# Sheet1.net
KiCad netlist of a schematic drawn in Altium Designer
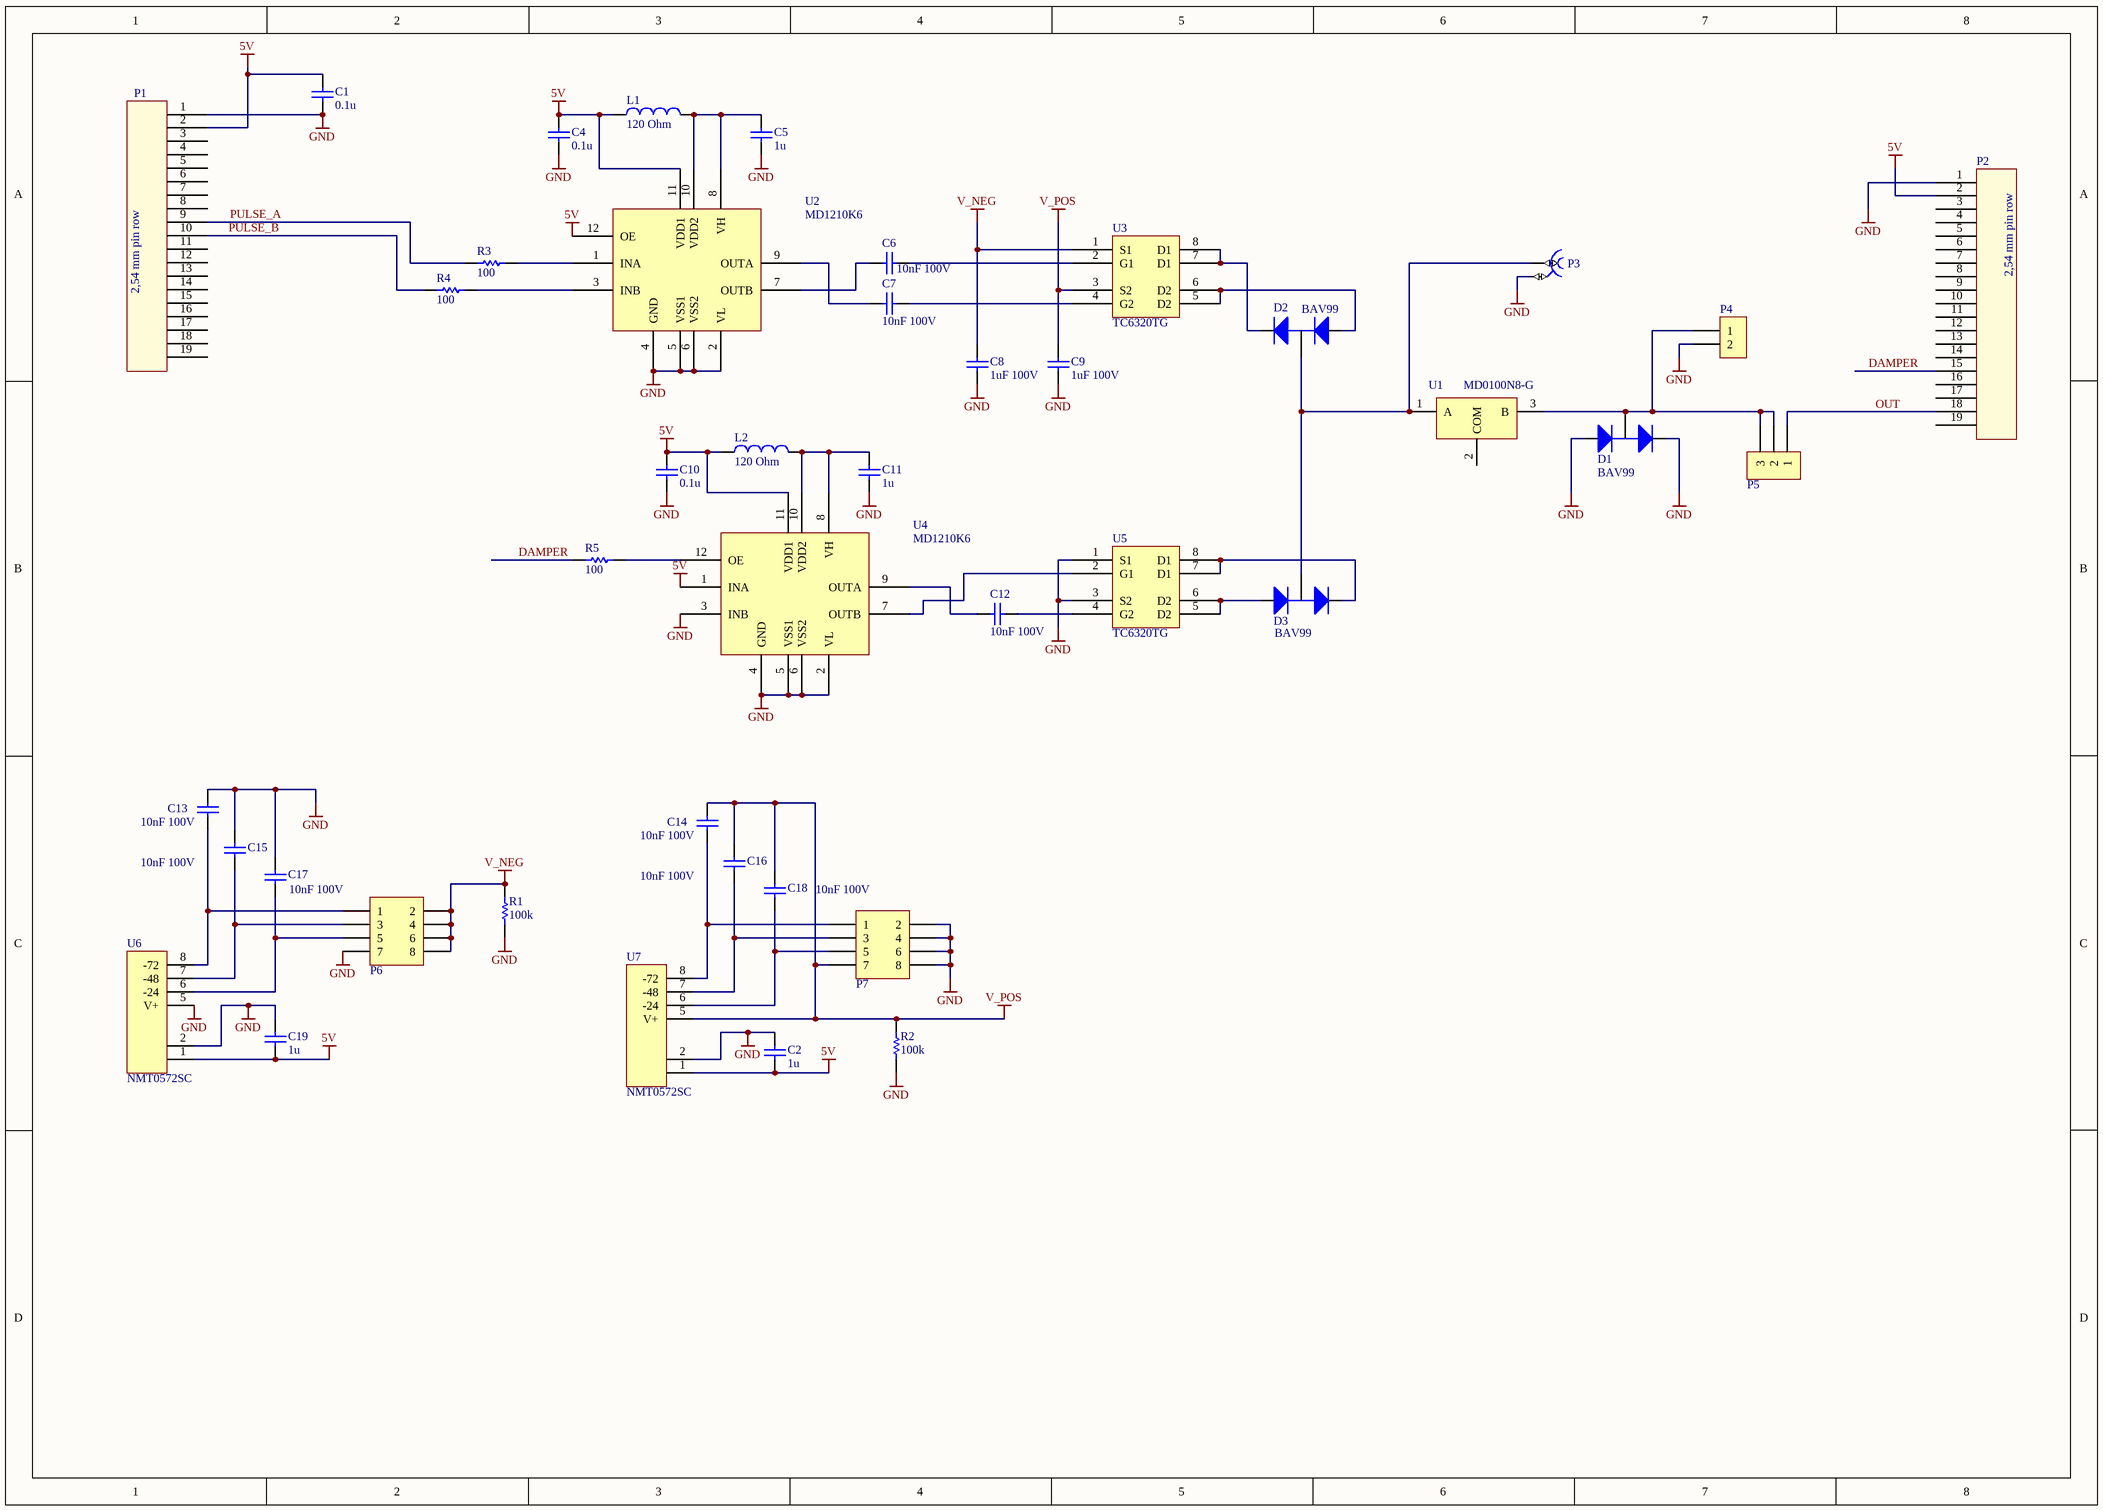
[diagram p0: Sheet1.SchDoc]

(export (version "E")
  (design (tool "Eeschema 10.0.6"))
  (components
    (comp (ref "C1")
      (value "0.1u")
      (footprint "0603RC")
      (description "Capacitor")
      (fields (field (name "PUBLISHER") "Altium Limited"))
      (libsource (lib "Miscellaneous Devices") (part "Cap"))
    )
    (comp (ref "C2")
      (value "1u")
      (footprint "0805RC")
      (description "Capacitor")
      (fields (field (name "PUBLISHER") "Altium Limited"))
      (libsource (lib "Miscellaneous Devices") (part "Cap"))
    )
    (comp (ref "C4")
      (value "0.1u")
      (footprint "0603RC")
      (description "Capacitor")
      (fields (field (name "PUBLISHER") "Altium Limited"))
      (libsource (lib "Miscellaneous Devices") (part "Cap"))
    )
    (comp (ref "C5")
      (value "1u")
      (footprint "0805RC")
      (description "Capacitor")
      (fields (field (name "PUBLISHER") "Altium Limited"))
      (libsource (lib "Miscellaneous Devices") (part "Cap"))
    )
    (comp (ref "C6")
      (value "10nF 100V")
      (footprint "0805RC")
      (description "Capacitor")
      (fields (field (name "PUBLISHER") "Altium Limited"))
      (libsource (lib "Miscellaneous Devices") (part "Cap"))
    )
    (comp (ref "C7")
      (value "10nF 100V")
      (footprint "0805RC")
      (description "Capacitor")
      (fields (field (name "PUBLISHER") "Altium Limited"))
      (libsource (lib "Miscellaneous Devices") (part "Cap"))
    )
    (comp (ref "C8")
      (value "1uF 100V")
      (footprint "1206RC")
      (description "Capacitor")
      (fields (field (name "PUBLISHER") "Altium Limited"))
      (libsource (lib "Miscellaneous Devices") (part "Cap"))
    )
    (comp (ref "C9")
      (value "1uF 100V")
      (footprint "1206RC")
      (description "Capacitor")
      (fields (field (name "PUBLISHER") "Altium Limited"))
      (libsource (lib "Miscellaneous Devices") (part "Cap"))
    )
    (comp (ref "C10")
      (value "0.1u")
      (footprint "0603RC")
      (description "Capacitor")
      (fields (field (name "PUBLISHER") "Altium Limited"))
      (libsource (lib "Miscellaneous Devices") (part "Cap"))
    )
    (comp (ref "C11")
      (value "1u")
      (footprint "0805RC")
      (description "Capacitor")
      (fields (field (name "PUBLISHER") "Altium Limited"))
      (libsource (lib "Miscellaneous Devices") (part "Cap"))
    )
    (comp (ref "C12")
      (value "10nF 100V")
      (footprint "0805RC")
      (description "Capacitor")
      (fields (field (name "PUBLISHER") "Altium Limited"))
      (libsource (lib "Miscellaneous Devices") (part "Cap"))
    )
    (comp (ref "C13")
      (value "10nF 100V")
      (footprint "0805RC")
      (description "Capacitor")
      (fields (field (name "PUBLISHER") "Altium Limited"))
      (libsource (lib "Miscellaneous Devices") (part "Cap"))
    )
    (comp (ref "C14")
      (value "10nF 100V")
      (footprint "0805RC")
      (description "Capacitor")
      (fields (field (name "PUBLISHER") "Altium Limited"))
      (libsource (lib "Miscellaneous Devices") (part "Cap"))
    )
    (comp (ref "C15")
      (value "10nF 100V")
      (footprint "0805RC")
      (description "Capacitor")
      (fields (field (name "PUBLISHER") "Altium Limited"))
      (libsource (lib "Miscellaneous Devices") (part "Cap"))
    )
    (comp (ref "C16")
      (value "10nF 100V")
      (footprint "0805RC")
      (description "Capacitor")
      (fields (field (name "PUBLISHER") "Altium Limited"))
      (libsource (lib "Miscellaneous Devices") (part "Cap"))
    )
    (comp (ref "C17")
      (value "10nF 100V")
      (footprint "0805RC")
      (description "Capacitor")
      (fields (field (name "PUBLISHER") "Altium Limited"))
      (libsource (lib "Miscellaneous Devices") (part "Cap"))
    )
    (comp (ref "C18")
      (value "10nF 100V")
      (footprint "0805RC")
      (description "Capacitor")
      (fields (field (name "PUBLISHER") "Altium Limited"))
      (libsource (lib "Miscellaneous Devices") (part "Cap"))
    )
    (comp (ref "C19")
      (value "1u")
      (footprint "0805RC")
      (description "Capacitor")
      (fields (field (name "PUBLISHER") "Altium Limited"))
      (libsource (lib "Miscellaneous Devices") (part "Cap"))
    )
    (comp (ref "D1")
      (value "BAV99")
      (footprint "SOT-23")
      (description "Medium-speed Switching Double Diode with Low Leakage Current")
      (fields (field (name "PUBLISHER") "Altium Limited"))
      (libsource (lib "Miscellaneous Devices") (part "BAV199"))
    )
    (comp (ref "D2")
      (value "BAV99")
      (footprint "SOT-23")
      (description "Medium-speed Switching Double Diode with Low Leakage Current")
      (fields (field (name "PUBLISHER") "Altium Limited"))
      (libsource (lib "Miscellaneous Devices") (part "BAV199"))
    )
    (comp (ref "D3")
      (value "BAV99")
      (footprint "SOT-23")
      (description "Medium-speed Switching Double Diode with Low Leakage Current")
      (fields (field (name "PUBLISHER") "Altium Limited"))
      (libsource (lib "Miscellaneous Devices") (part "BAV199"))
    )
    (comp (ref "L1")
      (value "120 Ohm")
      (footprint "0805R")
      (description "Inductor")
      (fields (field (name "Comment") "BLM21PG121SN1D") (field (name "PUBLISHER") "Altium Limited"))
      (libsource (lib "Miscellaneous Devices") (part "Inductor"))
    )
    (comp (ref "L2")
      (value "120 Ohm")
      (footprint "0805R")
      (description "Inductor")
      (fields (field (name "Comment") "BLM21PG121SN1D") (field (name "PUBLISHER") "Altium Limited"))
      (libsource (lib "Miscellaneous Devices") (part "Inductor"))
    )
    (comp (ref "P1")
      (value "PLS_2.54mm-19")
      (footprint "PLS_2.54mm-19")
      (libsource (lib "alt_vovan") (part "PLS_2.54mm-19"))
    )
    (comp (ref "P2")
      (value "PLS_2.54mm-19")
      (footprint "PLS_2.54mm-19")
      (libsource (lib "") (part "PLS_2.54mm-19_1"))
    )
    (comp (ref "P3")
      (value "SMA")
      (footprint "echOpen_ADC_Card:AMPHENOL_132357-11")
      (fields
        (field (name "PART NUMBER") "AMPHENOL_132357-11")
        (field (name "MANUFACTURER") "AMPHENOL")
        (field (name "MANUFACTURER PART NUMBER") "132357-11")
        (field (name "AUTHOR") "CERN DEM JLC")
      )
      (libsource (lib "Sof-Connectors") (part "Coax_1Female_1Shield"))
    )
    (comp (ref "P4")
      (value "SCSL-2")
      (footprint "SCSL-2")
      (description "2-pin general header")
      (fields (field (name "PUBLISHER") "Altium Limited"))
      (libsource (lib "Miscellaneous Devices") (part "Header 2"))
    )
    (comp (ref "P5")
      (value "PLS-3")
      (footprint "PLS-3")
      (description "3-pin general header")
      (fields (field (name "PUBLISHER") "Altium Limited"))
      (libsource (lib "Miscellaneous Devices") (part "Header 3"))
    )
    (comp (ref "P6")
      (value "PLD-8")
      (footprint "PLD-8")
      (description "Header, 4-Pin, Dual row")
      (fields (field (name "PUBLISHER") "Altium Limited"))
      (libsource (lib "Miscellaneous Devices") (part "Header 4X2"))
    )
    (comp (ref "P7")
      (value "PLD-8")
      (footprint "PLD-8")
      (description "Header, 4-Pin, Dual row")
      (fields (field (name "PUBLISHER") "Altium Limited"))
      (libsource (lib "Miscellaneous Devices") (part "Header 4X2"))
    )
    (comp (ref "R1")
      (value "100k")
      (footprint "0805R")
      (description "Resistor")
      (fields (field (name "PUBLISHER") "Altium Limited"))
      (libsource (lib "Miscellaneous Devices") (part "Res1"))
    )
    (comp (ref "R2")
      (value "100k")
      (footprint "0805R")
      (description "Resistor")
      (fields (field (name "PUBLISHER") "Altium Limited"))
      (libsource (lib "Miscellaneous Devices") (part "Res1"))
    )
    (comp (ref "R3")
      (value "100")
      (footprint "0603R")
      (description "Resistor")
      (fields (field (name "PUBLISHER") "Altium Limited"))
      (libsource (lib "Miscellaneous Devices") (part "Res1"))
    )
    (comp (ref "R4")
      (value "100")
      (footprint "0603R")
      (description "Resistor")
      (fields (field (name "PUBLISHER") "Altium Limited"))
      (libsource (lib "Miscellaneous Devices") (part "Res1"))
    )
    (comp (ref "R5")
      (value "100")
      (footprint "0603R")
      (description "Resistor")
      (fields (field (name "PUBLISHER") "Altium Limited"))
      (libsource (lib "Miscellaneous Devices") (part "Res1"))
    )
    (comp (ref "U1")
      (value "MD0100N8-G")
      (footprint "echOpen_ADC_Card:SOT89")
      (description "3-Ultra-Sound HV Switch 1=A 2=COM 3=B")
      (fields (field (name "MANUFACTURER") "Supertex inc.") (field (name "AUTHOR") "S. Jafar"))
      (libsource (lib "Sof-ICs And Semiconductors") (part "MD0100"))
    )
    (comp (ref "U2") (value "MD1210K6") (footprint "QFN-12 4x4mm") (libsource (lib "Pulser") (part "MD1210")))
    (comp (ref "U3")
      (value "TC6320TG")
      (footprint "SOIC127P600-8N")
      (description "N- and P-Channel  Enhancement-Mode MOSFET Pair")
      (libsource (lib "Pulser") (part "TC6320"))
    )
    (comp (ref "U4") (value "MD1210K6") (footprint "QFN-12 4x4mm") (libsource (lib "Pulser") (part "MD1210")))
    (comp (ref "U5")
      (value "TC6320TG")
      (footprint "SOIC127P600-8N")
      (description "N- and P-Channel  Enhancement-Mode MOSFET Pair")
      (libsource (lib "Pulser") (part "TC6320"))
    )
    (comp (ref "U6")
      (value "NMT0572SC")
      (footprint "NMT0572SC")
      (description "Horizontal")
      (fields (field (name "PUBLISHER") "Altium Limited"))
      (libsource (lib "Miscellaneous Devices") (part "Header 8"))
    )
    (comp (ref "U7")
      (value "NMT0572SC")
      (footprint "NMT0572SC")
      (description "Horizontal")
      (fields (field (name "PUBLISHER") "Altium Limited"))
      (libsource (lib "Miscellaneous Devices") (part "Header 8"))
    )
  )
  (nets
    (net (code "1") (name "/DAMPER") (class "Default")
      (node (ref "P2") (pin "15") (pinfunction "15_15") (pintype "passive"))
      (node (ref "R5") (pin "1") (pinfunction "1_1") (pintype "passive"))
    )
    (net (code "3") (name "/PULSE_A") (class "Default")
      (node (ref "P1") (pin "9") (pinfunction "9_9") (pintype "passive"))
      (node (ref "R3") (pin "1") (pinfunction "1_1") (pintype "passive"))
    )
    (net (code "4") (name "/PULSE_B") (class "Default")
      (node (ref "P1") (pin "10") (pinfunction "10_10") (pintype "passive"))
      (node (ref "R4") (pin "1") (pinfunction "1_1") (pintype "passive"))
    )
    (net (code "5") (name "5V") (class "Default")
      (node (ref "C1") (pin "2") (pinfunction "2_2") (pintype "passive"))
      (node (ref "C10") (pin "2") (pinfunction "2_2") (pintype "passive"))
      (node (ref "C19") (pin "1") (pinfunction "1_1") (pintype "passive"))
      (node (ref "C2") (pin "1") (pinfunction "1_1") (pintype "passive"))
      (node (ref "C4") (pin "2") (pinfunction "2_2") (pintype "passive"))
      (node (ref "L1") (pin "1") (pinfunction "1_1") (pintype "passive"))
      (node (ref "L2") (pin "1") (pinfunction "1_1") (pintype "passive"))
      (node (ref "P1") (pin "2") (pinfunction "2_2") (pintype "passive"))
      (node (ref "P2") (pin "2") (pinfunction "2_2") (pintype "passive"))
      (node (ref "U2") (pin "11") (pinfunction "VDD1_11") (pintype "passive"))
      (node (ref "U2") (pin "12") (pinfunction "OE_12") (pintype "passive"))
      (node (ref "U4") (pin "1") (pinfunction "INA_1") (pintype "passive"))
      (node (ref "U4") (pin "11") (pinfunction "VDD1_11") (pintype "passive"))
      (node (ref "U6") (pin "1") (pinfunction "1_1") (pintype "passive"))
      (node (ref "U7") (pin "1") (pinfunction "1_1") (pintype "passive"))
    )
    (net (code "6") (name "GND") (class "Default")
      (node (ref "C1") (pin "1") (pinfunction "1_1") (pintype "passive"))
      (node (ref "C10") (pin "1") (pinfunction "1_1") (pintype "passive"))
      (node (ref "C11") (pin "1") (pinfunction "1_1") (pintype "passive"))
      (node (ref "C13") (pin "1") (pinfunction "1_1") (pintype "passive"))
      (node (ref "C15") (pin "1") (pinfunction "1_1") (pintype "passive"))
      (node (ref "C17") (pin "1") (pinfunction "1_1") (pintype "passive"))
      (node (ref "C19") (pin "2") (pinfunction "2_2") (pintype "passive"))
      (node (ref "C2") (pin "2") (pinfunction "2_2") (pintype "passive"))
      (node (ref "C4") (pin "1") (pinfunction "1_1") (pintype "passive"))
      (node (ref "C5") (pin "1") (pinfunction "1_1") (pintype "passive"))
      (node (ref "C8") (pin "1") (pinfunction "1_1") (pintype "passive"))
      (node (ref "C9") (pin "1") (pinfunction "1_1") (pintype "passive"))
      (node (ref "D1") (pin "1") (pinfunction "A_1") (pintype "passive"))
      (node (ref "D1") (pin "2") (pinfunction "K_2") (pintype "passive"))
      (node (ref "P1") (pin "1") (pinfunction "1_1") (pintype "passive"))
      (node (ref "P2") (pin "1") (pinfunction "1_1") (pintype "passive"))
      (node (ref "P3") (pin "2") (pinfunction "2_2") (pintype "bidirectional"))
      (node (ref "P4") (pin "2") (pinfunction "2_2") (pintype "passive"))
      (node (ref "P6") (pin "7") (pinfunction "7_7") (pintype "passive"))
      (node (ref "P7") (pin "2") (pinfunction "2_2") (pintype "passive"))
      (node (ref "P7") (pin "4") (pinfunction "4_4") (pintype "passive"))
      (node (ref "P7") (pin "6") (pinfunction "6_6") (pintype "passive"))
      (node (ref "P7") (pin "8") (pinfunction "8_8") (pintype "passive"))
      (node (ref "R1") (pin "1") (pinfunction "1_1") (pintype "passive"))
      (node (ref "R2") (pin "1") (pinfunction "1_1") (pintype "passive"))
      (node (ref "U2") (pin "2") (pinfunction "VL_2") (pintype "passive"))
      (node (ref "U2") (pin "4") (pinfunction "GND_4") (pintype "passive"))
      (node (ref "U2") (pin "5") (pinfunction "VSS1_5") (pintype "passive"))
      (node (ref "U2") (pin "6") (pinfunction "VSS2_6") (pintype "passive"))
      (node (ref "U4") (pin "2") (pinfunction "VL_2") (pintype "passive"))
      (node (ref "U4") (pin "3") (pinfunction "INB_3") (pintype "passive"))
      (node (ref "U4") (pin "4") (pinfunction "GND_4") (pintype "passive"))
      (node (ref "U4") (pin "5") (pinfunction "VSS1_5") (pintype "passive"))
      (node (ref "U4") (pin "6") (pinfunction "VSS2_6") (pintype "passive"))
      (node (ref "U5") (pin "1") (pinfunction "S1_1") (pintype "passive"))
      (node (ref "U5") (pin "3") (pinfunction "S2_3") (pintype "passive"))
      (node (ref "U6") (pin "2") (pinfunction "2_2") (pintype "passive"))
      (node (ref "U6") (pin "5") (pinfunction "V+_5") (pintype "passive"))
      (node (ref "U7") (pin "2") (pinfunction "2_2") (pintype "passive"))
    )
    (net (code "7") (name "Net-(D1-C)") (class "Default")
      (node (ref "D1") (pin "3") (pinfunction "C_3") (pintype "passive"))
      (node (ref "P4") (pin "1") (pinfunction "1_1") (pintype "passive"))
      (node (ref "P5") (pin "2") (pinfunction "2_2") (pintype "passive"))
      (node (ref "P5") (pin "3") (pinfunction "3_3") (pintype "passive"))
      (node (ref "U1") (pin "3") (pinfunction "B_3") (pintype "passive"))
    )
    (net (code "8") (name "Net-(D2-A)") (class "Default")
      (node (ref "D2") (pin "1") (pinfunction "A_1") (pintype "passive"))
      (node (ref "U3") (pin "5") (pinfunction "D2_5") (pintype "passive"))
      (node (ref "U3") (pin "6") (pinfunction "D2_6") (pintype "passive"))
    )
    (net (code "9") (name "Net-(D2-C)") (class "Default")
      (node (ref "D2") (pin "3") (pinfunction "C_3") (pintype "passive"))
      (node (ref "D3") (pin "3") (pinfunction "C_3") (pintype "passive"))
      (node (ref "P3") (pin "1") (pinfunction "1_1") (pintype "bidirectional"))
      (node (ref "U1") (pin "1") (pinfunction "A_1") (pintype "passive"))
    )
    (net (code "10") (name "Net-(D2-K)") (class "Default")
      (node (ref "D2") (pin "2") (pinfunction "K_2") (pintype "passive"))
      (node (ref "U3") (pin "7") (pinfunction "D1_7") (pintype "passive"))
      (node (ref "U3") (pin "8") (pinfunction "D1_8") (pintype "passive"))
    )
    (net (code "11") (name "Net-(D3-A)") (class "Default")
      (node (ref "D3") (pin "1") (pinfunction "A_1") (pintype "passive"))
      (node (ref "U5") (pin "5") (pinfunction "D2_5") (pintype "passive"))
      (node (ref "U5") (pin "6") (pinfunction "D2_6") (pintype "passive"))
    )
    (net (code "12") (name "Net-(D3-K)") (class "Default")
      (node (ref "D3") (pin "2") (pinfunction "K_2") (pintype "passive"))
      (node (ref "U5") (pin "7") (pinfunction "D1_7") (pintype "passive"))
      (node (ref "U5") (pin "8") (pinfunction "D1_8") (pintype "passive"))
    )
    (net (code "13") (name "Net-(P2-Pad18)") (class "Default")
      (node (ref "P2") (pin "18") (pinfunction "18_18") (pintype "passive"))
      (node (ref "P5") (pin "1") (pinfunction "1_1") (pintype "passive"))
    )
    (net (code "14") (name "Net-(U2-INA)") (class "Default")
      (node (ref "R3") (pin "2") (pinfunction "2_2") (pintype "passive"))
      (node (ref "U2") (pin "1") (pinfunction "INA_1") (pintype "passive"))
    )
    (net (code "15") (name "Net-(U2-INB)") (class "Default")
      (node (ref "R4") (pin "2") (pinfunction "2_2") (pintype "passive"))
      (node (ref "U2") (pin "3") (pinfunction "INB_3") (pintype "passive"))
    )
    (net (code "16") (name "Net-(U2-OUTA)") (class "Default")
      (node (ref "C7") (pin "2") (pinfunction "2_2") (pintype "passive"))
      (node (ref "U2") (pin "9") (pinfunction "OUTA_9") (pintype "passive"))
    )
    (net (code "17") (name "Net-(U2-OUTB)") (class "Default")
      (node (ref "C6") (pin "2") (pinfunction "2_2") (pintype "passive"))
      (node (ref "U2") (pin "7") (pinfunction "OUTB_7") (pintype "passive"))
    )
    (net (code "18") (name "Net-(U2-VDD2)") (class "Default")
      (node (ref "C5") (pin "2") (pinfunction "2_2") (pintype "passive"))
      (node (ref "L1") (pin "2") (pinfunction "2_2") (pintype "passive"))
      (node (ref "U2") (pin "10") (pinfunction "VDD2_10") (pintype "passive"))
      (node (ref "U2") (pin "8") (pinfunction "VH_8") (pintype "passive"))
    )
    (net (code "19") (name "Net-(U3-G1)") (class "Default")
      (node (ref "C6") (pin "1") (pinfunction "1_1") (pintype "passive"))
      (node (ref "U3") (pin "2") (pinfunction "G1_2") (pintype "passive"))
    )
    (net (code "20") (name "Net-(U3-G2)") (class "Default")
      (node (ref "C7") (pin "1") (pinfunction "1_1") (pintype "passive"))
      (node (ref "U3") (pin "4") (pinfunction "G2_4") (pintype "passive"))
    )
    (net (code "21") (name "Net-(U4-OE)") (class "Default")
      (node (ref "R5") (pin "2") (pinfunction "2_2") (pintype "passive"))
      (node (ref "U4") (pin "12") (pinfunction "OE_12") (pintype "passive"))
    )
    (net (code "22") (name "Net-(U4-OUTA)") (class "Default")
      (node (ref "C12") (pin "2") (pinfunction "2_2") (pintype "passive"))
      (node (ref "U4") (pin "9") (pinfunction "OUTA_9") (pintype "passive"))
    )
    (net (code "23") (name "Net-(U4-OUTB)") (class "Default")
      (node (ref "U4") (pin "7") (pinfunction "OUTB_7") (pintype "passive"))
      (node (ref "U5") (pin "2") (pinfunction "G1_2") (pintype "passive"))
    )
    (net (code "24") (name "Net-(U4-VDD2)") (class "Default")
      (node (ref "C11") (pin "2") (pinfunction "2_2") (pintype "passive"))
      (node (ref "L2") (pin "2") (pinfunction "2_2") (pintype "passive"))
      (node (ref "U4") (pin "10") (pinfunction "VDD2_10") (pintype "passive"))
      (node (ref "U4") (pin "8") (pinfunction "VH_8") (pintype "passive"))
    )
    (net (code "25") (name "Net-(U5-G2)") (class "Default")
      (node (ref "C12") (pin "1") (pinfunction "1_1") (pintype "passive"))
      (node (ref "U5") (pin "4") (pinfunction "G2_4") (pintype "passive"))
    )
    (net (code "26") (name "Net-(U6--24)") (class "Default")
      (node (ref "C17") (pin "2") (pinfunction "2_2") (pintype "passive"))
      (node (ref "P6") (pin "5") (pinfunction "5_5") (pintype "passive"))
      (node (ref "U6") (pin "6") (pinfunction "-24_6") (pintype "passive"))
    )
    (net (code "27") (name "Net-(U6--48)") (class "Default")
      (node (ref "C15") (pin "2") (pinfunction "2_2") (pintype "passive"))
      (node (ref "P6") (pin "3") (pinfunction "3_3") (pintype "passive"))
      (node (ref "U6") (pin "7") (pinfunction "-48_7") (pintype "passive"))
    )
    (net (code "28") (name "Net-(U6--72)") (class "Default")
      (node (ref "C13") (pin "2") (pinfunction "2_2") (pintype "passive"))
      (node (ref "P6") (pin "1") (pinfunction "1_1") (pintype "passive"))
      (node (ref "U6") (pin "8") (pinfunction "-72_8") (pintype "passive"))
    )
    (net (code "29") (name "Net-(U7--24)") (class "Default")
      (node (ref "C18") (pin "2") (pinfunction "2_2") (pintype "passive"))
      (node (ref "P7") (pin "5") (pinfunction "5_5") (pintype "passive"))
      (node (ref "U7") (pin "6") (pinfunction "-24_6") (pintype "passive"))
    )
    (net (code "30") (name "Net-(U7--48)") (class "Default")
      (node (ref "C16") (pin "2") (pinfunction "2_2") (pintype "passive"))
      (node (ref "P7") (pin "3") (pinfunction "3_3") (pintype "passive"))
      (node (ref "U7") (pin "7") (pinfunction "-48_7") (pintype "passive"))
    )
    (net (code "31") (name "Net-(U7--72)") (class "Default")
      (node (ref "C14") (pin "2") (pinfunction "2_2") (pintype "passive"))
      (node (ref "P7") (pin "1") (pinfunction "1_1") (pintype "passive"))
      (node (ref "U7") (pin "8") (pinfunction "-72_8") (pintype "passive"))
    )
    (net (code "32") (name "V_NEG") (class "Default")
      (node (ref "C8") (pin "2") (pinfunction "2_2") (pintype "passive"))
      (node (ref "P6") (pin "2") (pinfunction "2_2") (pintype "passive"))
      (node (ref "P6") (pin "4") (pinfunction "4_4") (pintype "passive"))
      (node (ref "P6") (pin "6") (pinfunction "6_6") (pintype "passive"))
      (node (ref "P6") (pin "8") (pinfunction "8_8") (pintype "passive"))
      (node (ref "R1") (pin "2") (pinfunction "2_2") (pintype "passive"))
      (node (ref "U3") (pin "1") (pinfunction "S1_1") (pintype "passive"))
    )
    (net (code "33") (name "V_POS") (class "Default")
      (node (ref "C14") (pin "1") (pinfunction "1_1") (pintype "passive"))
      (node (ref "C16") (pin "1") (pinfunction "1_1") (pintype "passive"))
      (node (ref "C18") (pin "1") (pinfunction "1_1") (pintype "passive"))
      (node (ref "C9") (pin "2") (pinfunction "2_2") (pintype "passive"))
      (node (ref "P7") (pin "7") (pinfunction "7_7") (pintype "passive"))
      (node (ref "R2") (pin "2") (pinfunction "2_2") (pintype "passive"))
      (node (ref "U3") (pin "3") (pinfunction "S2_3") (pintype "passive"))
      (node (ref "U7") (pin "5") (pinfunction "V+_5") (pintype "passive"))
    )
    (net (code "34") (name "unconnected-(P1-Pad3)") (class "Default")
      (node (ref "P1") (pin "3") (pinfunction "3_3") (pintype "passive"))
    )
    (net (code "35") (name "unconnected-(P1-Pad4)") (class "Default")
      (node (ref "P1") (pin "4") (pinfunction "4_4") (pintype "passive"))
    )
    (net (code "36") (name "unconnected-(P1-Pad5)") (class "Default")
      (node (ref "P1") (pin "5") (pinfunction "5_5") (pintype "passive"))
    )
    (net (code "37") (name "unconnected-(P1-Pad6)") (class "Default")
      (node (ref "P1") (pin "6") (pinfunction "6_6") (pintype "passive"))
    )
    (net (code "38") (name "unconnected-(P1-Pad7)") (class "Default")
      (node (ref "P1") (pin "7") (pinfunction "7_7") (pintype "passive"))
    )
    (net (code "39") (name "unconnected-(P1-Pad8)") (class "Default")
      (node (ref "P1") (pin "8") (pinfunction "8_8") (pintype "passive"))
    )
    (net (code "40") (name "unconnected-(P1-Pad11)") (class "Default")
      (node (ref "P1") (pin "11") (pinfunction "11_11") (pintype "passive"))
    )
    (net (code "41") (name "unconnected-(P1-Pad12)") (class "Default")
      (node (ref "P1") (pin "12") (pinfunction "12_12") (pintype "passive"))
    )
    (net (code "42") (name "unconnected-(P1-Pad13)") (class "Default")
      (node (ref "P1") (pin "13") (pinfunction "13_13") (pintype "passive"))
    )
    (net (code "43") (name "unconnected-(P1-Pad14)") (class "Default")
      (node (ref "P1") (pin "14") (pinfunction "14_14") (pintype "passive"))
    )
    (net (code "44") (name "unconnected-(P1-Pad15)") (class "Default")
      (node (ref "P1") (pin "15") (pinfunction "15_15") (pintype "passive"))
    )
    (net (code "45") (name "unconnected-(P1-Pad16)") (class "Default")
      (node (ref "P1") (pin "16") (pinfunction "16_16") (pintype "passive"))
    )
    (net (code "46") (name "unconnected-(P1-Pad17)") (class "Default")
      (node (ref "P1") (pin "17") (pinfunction "17_17") (pintype "passive"))
    )
    (net (code "47") (name "unconnected-(P1-Pad18)") (class "Default")
      (node (ref "P1") (pin "18") (pinfunction "18_18") (pintype "passive"))
    )
    (net (code "48") (name "unconnected-(P1-Pad19)") (class "Default")
      (node (ref "P1") (pin "19") (pinfunction "19_19") (pintype "passive"))
    )
    (net (code "49") (name "unconnected-(P2-Pad3)") (class "Default")
      (node (ref "P2") (pin "3") (pinfunction "3_3") (pintype "passive"))
    )
    (net (code "50") (name "unconnected-(P2-Pad4)") (class "Default")
      (node (ref "P2") (pin "4") (pinfunction "4_4") (pintype "passive"))
    )
    (net (code "51") (name "unconnected-(P2-Pad5)") (class "Default")
      (node (ref "P2") (pin "5") (pinfunction "5_5") (pintype "passive"))
    )
    (net (code "52") (name "unconnected-(P2-Pad6)") (class "Default")
      (node (ref "P2") (pin "6") (pinfunction "6_6") (pintype "passive"))
    )
    (net (code "53") (name "unconnected-(P2-Pad7)") (class "Default")
      (node (ref "P2") (pin "7") (pinfunction "7_7") (pintype "passive"))
    )
    (net (code "54") (name "unconnected-(P2-Pad8)") (class "Default")
      (node (ref "P2") (pin "8") (pinfunction "8_8") (pintype "passive"))
    )
    (net (code "55") (name "unconnected-(P2-Pad9)") (class "Default")
      (node (ref "P2") (pin "9") (pinfunction "9_9") (pintype "passive"))
    )
    (net (code "56") (name "unconnected-(P2-Pad10)") (class "Default")
      (node (ref "P2") (pin "10") (pinfunction "10_10") (pintype "passive"))
    )
    (net (code "57") (name "unconnected-(P2-Pad11)") (class "Default")
      (node (ref "P2") (pin "11") (pinfunction "11_11") (pintype "passive"))
    )
    (net (code "58") (name "unconnected-(P2-Pad12)") (class "Default")
      (node (ref "P2") (pin "12") (pinfunction "12_12") (pintype "passive"))
    )
    (net (code "59") (name "unconnected-(P2-Pad13)") (class "Default")
      (node (ref "P2") (pin "13") (pinfunction "13_13") (pintype "passive"))
    )
    (net (code "60") (name "unconnected-(P2-Pad14)") (class "Default")
      (node (ref "P2") (pin "14") (pinfunction "14_14") (pintype "passive"))
    )
    (net (code "61") (name "unconnected-(P2-Pad16)") (class "Default")
      (node (ref "P2") (pin "16") (pinfunction "16_16") (pintype "passive"))
    )
    (net (code "62") (name "unconnected-(P2-Pad17)") (class "Default")
      (node (ref "P2") (pin "17") (pinfunction "17_17") (pintype "passive"))
    )
    (net (code "63") (name "unconnected-(P2-Pad19)") (class "Default")
      (node (ref "P2") (pin "19") (pinfunction "19_19") (pintype "passive"))
    )
    (net (code "64") (name "unconnected-(U1-COM-Pad2)") (class "Default")
      (node (ref "U1") (pin "2") (pinfunction "COM_2") (pintype "passive"))
    )
    (net (code "65") (name "unconnected-(U6-Pad3)") (class "Default")
      (node (ref "U6") (pin "3") (pinfunction "3_3") (pintype "passive"))
    )
    (net (code "66") (name "unconnected-(U6-Pad4)") (class "Default")
      (node (ref "U6") (pin "4") (pinfunction "4_4") (pintype "passive"))
    )
    (net (code "67") (name "unconnected-(U7-Pad3)") (class "Default")
      (node (ref "U7") (pin "3") (pinfunction "3_3") (pintype "passive"))
    )
    (net (code "68") (name "unconnected-(U7-Pad4)") (class "Default")
      (node (ref "U7") (pin "4") (pinfunction "4_4") (pintype "passive"))
    )
  )
)
